# nrf24-breakout.net
KiCad netlist of a schematic drawn in EAGLE
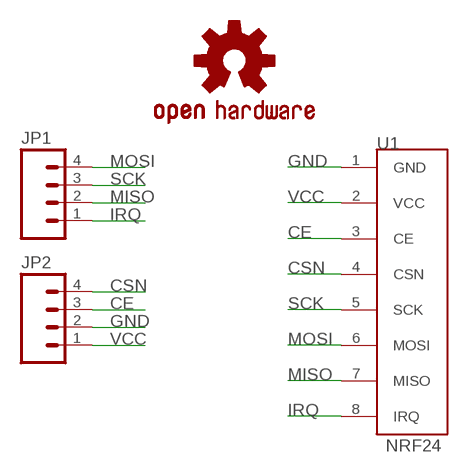
[diagram p0: schematic, sheet 1]

(export (version "E")
  (design (tool "Eeschema 10.0.6"))
  (components
    (comp (ref "JP1")
      (value "M04NO_SILK_ALL_ROUND")
      (footprint "eagle-import:1X04_NO_SILK_ALL_ROUND")
      (libsource (lib "eagle-import") (part "M04NO_SILK_ALL_ROUND"))
    )
    (comp (ref "JP2")
      (value "M04NO_SILK_ALL_ROUND")
      (footprint "eagle-import:1X04_NO_SILK_ALL_ROUND")
      (libsource (lib "eagle-import") (part "M04NO_SILK_ALL_ROUND"))
    )
    (comp (ref "LOGO1")
      (value "OSHW-LOGOS")
      (footprint "eagle-import:OSHW-LOGO-S")
      (libsource (lib "eagle-import") (part "OSHW-LOGOS"))
    )
    (comp (ref "U1")
      (value "NRF24")
      (footprint "eagle-import:NRF24")
      (libsource (lib "eagle-import") (part "NRF24"))
    )
  )
  (nets
    (net (code "1") (name "/CE") (class "Default")
      (node (ref "JP2") (pin "3") (pinfunction "3_3") (pintype "passive"))
      (node (ref "U1") (pin "3") (pinfunction "CE_3") (pintype "bidirectional"))
    )
    (net (code "2") (name "/CSN") (class "Default")
      (node (ref "JP2") (pin "4") (pinfunction "4_4") (pintype "passive"))
      (node (ref "U1") (pin "4") (pinfunction "CSN_4") (pintype "bidirectional"))
    )
    (net (code "3") (name "/GND") (class "Default")
      (node (ref "JP2") (pin "2") (pinfunction "2_2") (pintype "passive"))
      (node (ref "U1") (pin "1") (pinfunction "GND_1") (pintype "bidirectional"))
    )
    (net (code "4") (name "/IRQ") (class "Default")
      (node (ref "JP1") (pin "1") (pinfunction "1_1") (pintype "passive"))
      (node (ref "U1") (pin "8") (pinfunction "IRQ_8") (pintype "bidirectional"))
    )
    (net (code "5") (name "/MISO") (class "Default")
      (node (ref "JP1") (pin "2") (pinfunction "2_2") (pintype "passive"))
      (node (ref "U1") (pin "7") (pinfunction "MISO_7") (pintype "bidirectional"))
    )
    (net (code "6") (name "/MOSI") (class "Default")
      (node (ref "JP1") (pin "4") (pinfunction "4_4") (pintype "passive"))
      (node (ref "U1") (pin "6") (pinfunction "MOSI_6") (pintype "bidirectional"))
    )
    (net (code "7") (name "/SCK") (class "Default")
      (node (ref "JP1") (pin "3") (pinfunction "3_3") (pintype "passive"))
      (node (ref "U1") (pin "5") (pinfunction "SCK_5") (pintype "bidirectional"))
    )
    (net (code "8") (name "/VCC") (class "Default")
      (node (ref "JP2") (pin "1") (pinfunction "1_1") (pintype "passive"))
      (node (ref "U1") (pin "2") (pinfunction "VCC_2") (pintype "bidirectional"))
    )
  )
)
